# big_seven_control_v0_1.net
KiCad netlist of a schematic drawn in EAGLE
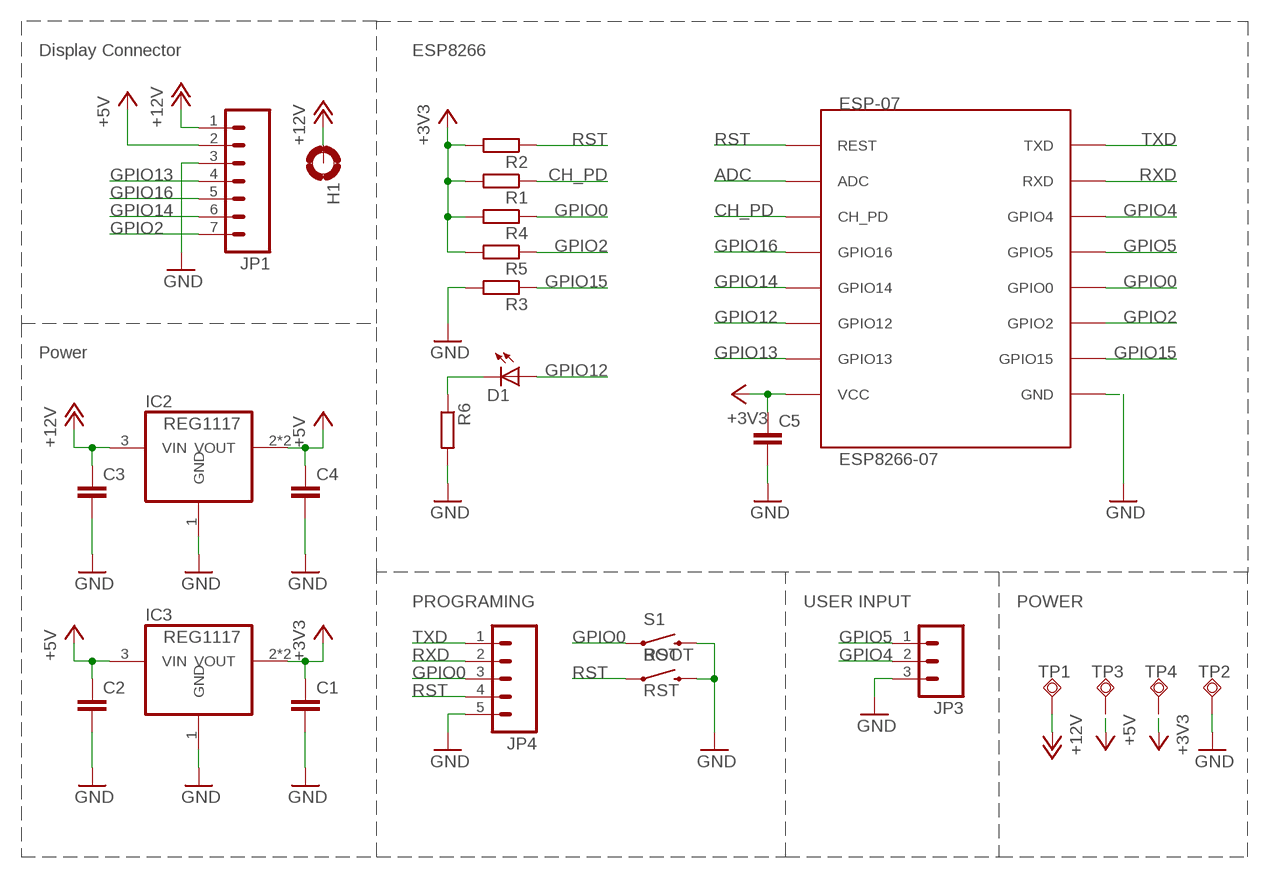
[diagram p0: schematic, sheet 1]

(export (version "E")
  (design (tool "Eeschema 10.0.6"))
  (components
    (comp (ref "C1")
      (value "C-EUC1206K")
      (footprint "eagle-import:C1206K")
      (libsource (lib "eagle-import") (part "C-EUC1206K"))
    )
    (comp (ref "C2")
      (value "C-EUC1206K")
      (footprint "eagle-import:C1206K")
      (libsource (lib "eagle-import") (part "C-EUC1206K"))
    )
    (comp (ref "C3")
      (value "C-EUC1206K")
      (footprint "eagle-import:C1206K")
      (libsource (lib "eagle-import") (part "C-EUC1206K"))
    )
    (comp (ref "C4")
      (value "C-EUC1206K")
      (footprint "eagle-import:C1206K")
      (libsource (lib "eagle-import") (part "C-EUC1206K"))
    )
    (comp (ref "C5")
      (value "C-EUC0805")
      (footprint "eagle-import:C0805")
      (libsource (lib "eagle-import") (part "C-EUC0805"))
    )
    (comp (ref "D1")
      (value "LEDCHIP-LED0805")
      (footprint "eagle-import:CHIP-LED0805")
      (libsource (lib "eagle-import") (part "LEDCHIP-LED0805"))
    )
    (comp (ref "ESP-07")
      (value "ESP8266-07")
      (footprint "eagle-import:ESP-07")
      (libsource (lib "eagle-import") (part "ESP8266-07"))
    )
    (comp (ref "H1")
      (value "MOUNT-PAD-ROUND3.2")
      (footprint "eagle-import:3,2-PAD")
      (libsource (lib "eagle-import") (part "MOUNT-PAD-ROUND3.2"))
    )
    (comp (ref "IC2")
      (value "REG1117")
      (footprint "eagle-import:SOT223")
      (libsource (lib "eagle-import") (part "REG1117"))
    )
    (comp (ref "IC3")
      (value "REG1117")
      (footprint "eagle-import:SOT223")
      (libsource (lib "eagle-import") (part "REG1117"))
    )
    (comp (ref "JP1")
      (value "M07LOCK")
      (footprint "eagle-import:1X07_LOCK")
      (libsource (lib "eagle-import") (part "M07LOCK"))
    )
    (comp (ref "JP3")
      (value "M03LOCK")
      (footprint "eagle-import:1X03_LOCK")
      (libsource (lib "eagle-import") (part "M03LOCK"))
    )
    (comp (ref "JP4")
      (value "M05LOCK")
      (footprint "eagle-import:1X05_LOCK")
      (libsource (lib "eagle-import") (part "M05LOCK"))
    )
    (comp (ref "R1")
      (value "R-EU_R0805")
      (footprint "eagle-import:R0805")
      (libsource (lib "eagle-import") (part "R-EU_R0805"))
    )
    (comp (ref "R2")
      (value "R-EU_R0805")
      (footprint "eagle-import:R0805")
      (libsource (lib "eagle-import") (part "R-EU_R0805"))
    )
    (comp (ref "R3")
      (value "R-EU_R0805")
      (footprint "eagle-import:R0805")
      (libsource (lib "eagle-import") (part "R-EU_R0805"))
    )
    (comp (ref "R4")
      (value "R-EU_R0805")
      (footprint "eagle-import:R0805")
      (libsource (lib "eagle-import") (part "R-EU_R0805"))
    )
    (comp (ref "R5")
      (value "R-EU_R0805")
      (footprint "eagle-import:R0805")
      (libsource (lib "eagle-import") (part "R-EU_R0805"))
    )
    (comp (ref "R6")
      (value "R-EU_R0805")
      (footprint "eagle-import:R0805")
      (libsource (lib "eagle-import") (part "R-EU_R0805"))
    )
    (comp (ref "RST")
      (value "RST")
      (footprint "eagle-import:TACTILE-SWITCH-SMD")
      (libsource (lib "eagle-import") (part "SWITCH-MOMENTARY-2SMD"))
    )
    (comp (ref "S1")
      (value "BOOT")
      (footprint "eagle-import:TACTILE-SWITCH-SMD")
      (libsource (lib "eagle-import") (part "SWITCH-MOMENTARY-2SMD"))
    )
    (comp (ref "TP1")
      (value "12V")
      (footprint "eagle-import:TP20R")
      (libsource (lib "eagle-import") (part "TPSQTP20R"))
    )
    (comp (ref "TP2")
      (value "delk")
      (footprint "eagle-import:TP20R")
      (libsource (lib "eagle-import") (part "TPSQTP20R"))
    )
    (comp (ref "TP3")
      (value "5V")
      (footprint "eagle-import:TP20R")
      (libsource (lib "eagle-import") (part "TPSQTP20R"))
    )
    (comp (ref "TP4")
      (value "3V3")
      (footprint "eagle-import:TP20R")
      (libsource (lib "eagle-import") (part "TPSQTP20R"))
    )
  )
  (nets
    (net (code "1") (name "+3V3") (class "Default")
      (node (ref "C1") (pin "1") (pinfunction "1_1") (pintype "passive"))
      (node (ref "C5") (pin "1") (pinfunction "1_1") (pintype "passive"))
      (node (ref "ESP-07") (pin "VCC") (pinfunction "VCC_VCC") (pintype "power_in"))
      (node (ref "IC3") (pin "2") (pinfunction "VOUT_2") (pintype "output"))
      (node (ref "IC3") (pin "4") (pinfunction "VOUT_4") (pintype "output"))
      (node (ref "R1") (pin "2") (pinfunction "2_2") (pintype "passive"))
      (node (ref "R2") (pin "2") (pinfunction "2_2") (pintype "passive"))
      (node (ref "R4") (pin "2") (pinfunction "2_2") (pintype "passive"))
      (node (ref "R5") (pin "2") (pinfunction "2_2") (pintype "passive"))
      (node (ref "TP4") (pin "TP") (pinfunction "TP_TP") (pintype "input"))
    )
    (net (code "2") (name "+5V") (class "Default")
      (node (ref "C2") (pin "1") (pinfunction "1_1") (pintype "passive"))
      (node (ref "C4") (pin "1") (pinfunction "1_1") (pintype "passive"))
      (node (ref "IC2") (pin "2") (pinfunction "VOUT_2") (pintype "output"))
      (node (ref "IC2") (pin "4") (pinfunction "VOUT_4") (pintype "output"))
      (node (ref "IC3") (pin "3") (pinfunction "VIN_3") (pintype "input"))
      (node (ref "JP1") (pin "2") (pinfunction "2_2") (pintype "passive"))
      (node (ref "TP3") (pin "TP") (pinfunction "TP_TP") (pintype "input"))
    )
    (net (code "3") (name "+12V") (class "Default")
      (node (ref "C3") (pin "1") (pinfunction "1_1") (pintype "passive"))
      (node (ref "H1") (pin "B3,2") (pinfunction "MOUNT_B3,2") (pintype "passive"))
      (node (ref "IC2") (pin "3") (pinfunction "VIN_3") (pintype "input"))
      (node (ref "JP1") (pin "1") (pinfunction "1_1") (pintype "passive"))
      (node (ref "TP1") (pin "TP") (pinfunction "TP_TP") (pintype "input"))
    )
    (net (code "4") (name "/ADC") (class "Default")
      (node (ref "ESP-07") (pin "ADC") (pinfunction "ADC_ADC") (pintype "bidirectional"))
    )
    (net (code "5") (name "/CH_PD") (class "Default")
      (node (ref "ESP-07") (pin "CH_PD") (pinfunction "CH_PD_CH_PD") (pintype "input"))
      (node (ref "R1") (pin "1") (pinfunction "1_1") (pintype "passive"))
    )
    (net (code "6") (name "/GPIO0") (class "Default")
      (node (ref "ESP-07") (pin "GPIO0") (pinfunction "GPIO0_GPIO0") (pintype "bidirectional"))
      (node (ref "JP4") (pin "3") (pinfunction "3_3") (pintype "passive"))
      (node (ref "R4") (pin "1") (pinfunction "1_1") (pintype "passive"))
      (node (ref "S1") (pin "1") (pinfunction "1_1") (pintype "passive"))
    )
    (net (code "7") (name "/GPIO2") (class "Default")
      (node (ref "ESP-07") (pin "GPIO2") (pinfunction "GPIO2_GPIO2") (pintype "bidirectional"))
      (node (ref "JP1") (pin "7") (pinfunction "7_7") (pintype "passive"))
      (node (ref "R5") (pin "1") (pinfunction "1_1") (pintype "passive"))
    )
    (net (code "8") (name "/GPIO4") (class "Default")
      (node (ref "ESP-07") (pin "GPIO4") (pinfunction "GPIO4_GPIO4") (pintype "bidirectional"))
      (node (ref "JP3") (pin "2") (pinfunction "2_2") (pintype "passive"))
    )
    (net (code "9") (name "/GPIO5") (class "Default")
      (node (ref "ESP-07") (pin "GPIO5") (pinfunction "GPIO5_GPIO5") (pintype "bidirectional"))
      (node (ref "JP3") (pin "1") (pinfunction "1_1") (pintype "passive"))
    )
    (net (code "10") (name "/GPIO12") (class "Default")
      (node (ref "D1") (pin "A") (pinfunction "A_A") (pintype "passive"))
      (node (ref "ESP-07") (pin "GPIO12") (pinfunction "GPIO12_GPIO12") (pintype "bidirectional"))
    )
    (net (code "11") (name "/GPIO13") (class "Default")
      (node (ref "ESP-07") (pin "GPIO13") (pinfunction "GPIO13_GPIO13") (pintype "bidirectional"))
      (node (ref "JP1") (pin "4") (pinfunction "4_4") (pintype "passive"))
    )
    (net (code "12") (name "/GPIO14") (class "Default")
      (node (ref "ESP-07") (pin "GPIO14") (pinfunction "GPIO14_GPIO14") (pintype "bidirectional"))
      (node (ref "JP1") (pin "5") (pinfunction "5_5") (pintype "passive"))
    )
    (net (code "13") (name "/GPIO15") (class "Default")
      (node (ref "ESP-07") (pin "GPIO15") (pinfunction "GPIO15_GPIO15") (pintype "input"))
      (node (ref "R3") (pin "1") (pinfunction "1_1") (pintype "passive"))
    )
    (net (code "14") (name "/GPIO16") (class "Default")
      (node (ref "ESP-07") (pin "GPIO16") (pinfunction "GPIO16_GPIO16") (pintype "bidirectional"))
      (node (ref "JP1") (pin "6") (pinfunction "6_6") (pintype "passive"))
    )
    (net (code "15") (name "/RST") (class "Default")
      (node (ref "ESP-07") (pin "REST") (pinfunction "REST_REST") (pintype "bidirectional"))
      (node (ref "JP4") (pin "4") (pinfunction "4_4") (pintype "passive"))
      (node (ref "R2") (pin "1") (pinfunction "1_1") (pintype "passive"))
      (node (ref "RST") (pin "1") (pinfunction "1_1") (pintype "passive"))
    )
    (net (code "16") (name "/RXD") (class "Default")
      (node (ref "ESP-07") (pin "RXD") (pinfunction "RXD_RXD") (pintype "input"))
      (node (ref "JP4") (pin "2") (pinfunction "2_2") (pintype "passive"))
    )
    (net (code "17") (name "/TXD") (class "Default")
      (node (ref "ESP-07") (pin "TXD") (pinfunction "TXD_TXD") (pintype "output"))
      (node (ref "JP4") (pin "1") (pinfunction "1_1") (pintype "passive"))
    )
    (net (code "18") (name "GND") (class "Default")
      (node (ref "C1") (pin "2") (pinfunction "2_2") (pintype "passive"))
      (node (ref "C2") (pin "2") (pinfunction "2_2") (pintype "passive"))
      (node (ref "C3") (pin "2") (pinfunction "2_2") (pintype "passive"))
      (node (ref "C4") (pin "2") (pinfunction "2_2") (pintype "passive"))
      (node (ref "C5") (pin "2") (pinfunction "2_2") (pintype "passive"))
      (node (ref "ESP-07") (pin "GND") (pinfunction "GND_GND") (pintype "power_in"))
      (node (ref "IC2") (pin "1") (pinfunction "GND_1") (pintype "power_in"))
      (node (ref "IC3") (pin "1") (pinfunction "GND_1") (pintype "power_in"))
      (node (ref "JP1") (pin "3") (pinfunction "3_3") (pintype "passive"))
      (node (ref "JP3") (pin "3") (pinfunction "3_3") (pintype "passive"))
      (node (ref "JP4") (pin "5") (pinfunction "5_5") (pintype "passive"))
      (node (ref "R3") (pin "2") (pinfunction "2_2") (pintype "passive"))
      (node (ref "R6") (pin "2") (pinfunction "2_2") (pintype "passive"))
      (node (ref "RST") (pin "3") (pinfunction "2_3") (pintype "passive"))
      (node (ref "S1") (pin "3") (pinfunction "2_3") (pintype "passive"))
      (node (ref "TP2") (pin "TP") (pinfunction "TP_TP") (pintype "input"))
    )
    (net (code "19") (name "Net-(D1-PadC)") (class "Default")
      (node (ref "D1") (pin "C") (pinfunction "C_C") (pintype "passive"))
      (node (ref "R6") (pin "1") (pinfunction "1_1") (pintype "passive"))
    )
  )
)
